# Telemetria.net
KiCad netlist of a schematic drawn in EAGLE
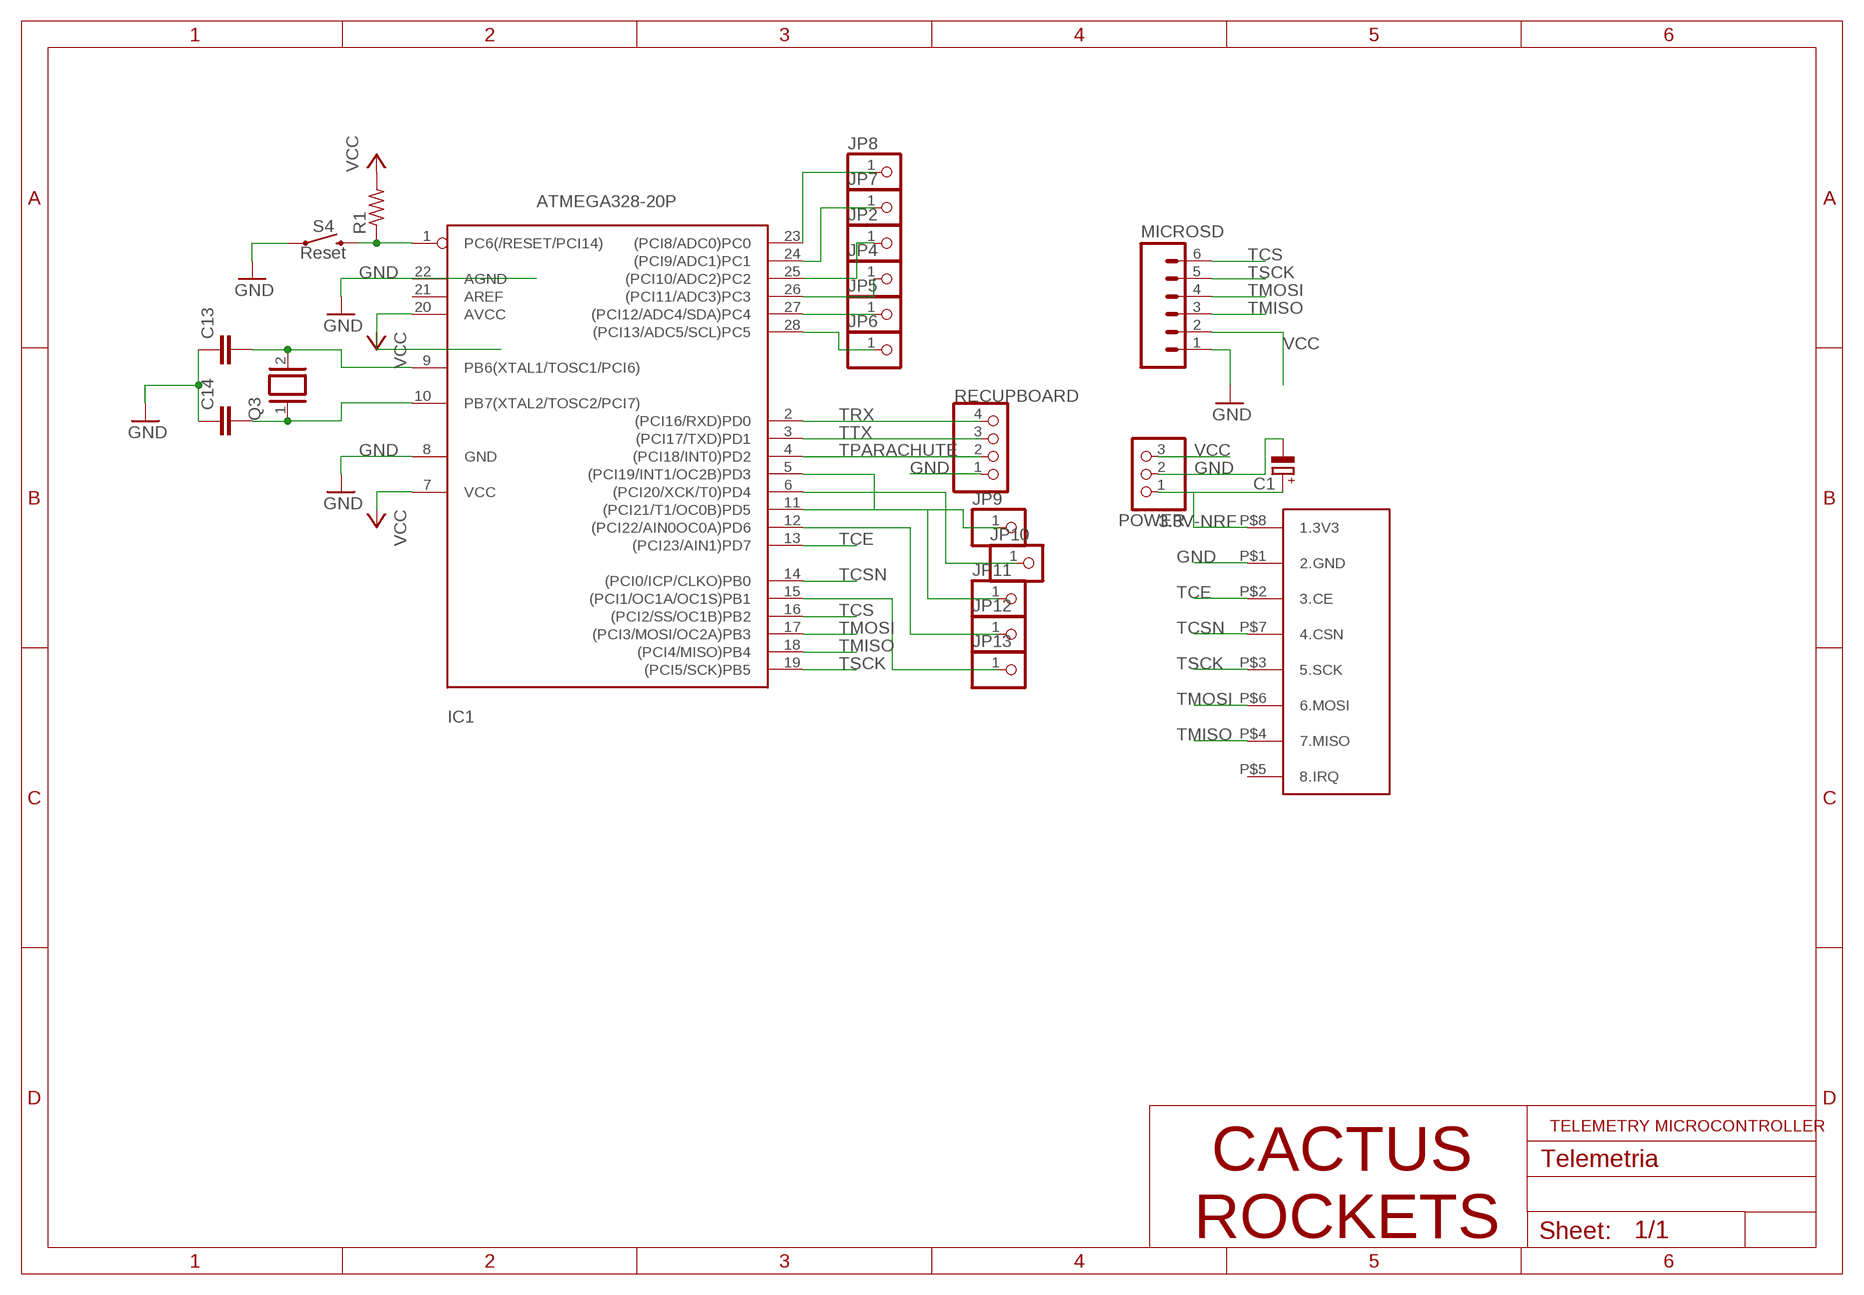
[diagram p0: schematic, sheet 1]

(export (version "E")
  (design (tool "Eeschema 10.0.6"))
  (components
    (comp (ref "C1")
      (value "CPOL-EUE1.8-4")
      (footprint "eagle-import:E1,8-4")
      (libsource (lib "eagle-import") (part "CPOL-EUE1.8-4"))
    )
    (comp (ref "C13")
      (value "C-EU025-025X050")
      (footprint "eagle-import:C025-025X050")
      (libsource (lib "eagle-import") (part "C-EU025-025X050"))
    )
    (comp (ref "C14")
      (value "C-EU025-025X050")
      (footprint "eagle-import:C025-025X050")
      (libsource (lib "eagle-import") (part "C-EU025-025X050"))
    )
    (comp (ref "IC1")
      (value "ATMEGA328-20P")
      (footprint "eagle-import:DIL28-3")
      (libsource (lib "eagle-import") (part "ATMEGA328P-20"))
    )
    (comp (ref "JP2")
      (value "PINHD-1X1")
      (footprint "eagle-import:1X01")
      (libsource (lib "eagle-import") (part "PINHD-1X1"))
    )
    (comp (ref "JP4")
      (value "PINHD-1X1")
      (footprint "eagle-import:1X01")
      (libsource (lib "eagle-import") (part "PINHD-1X1"))
    )
    (comp (ref "JP5")
      (value "PINHD-1X1")
      (footprint "eagle-import:1X01")
      (libsource (lib "eagle-import") (part "PINHD-1X1"))
    )
    (comp (ref "JP6")
      (value "PINHD-1X1")
      (footprint "eagle-import:1X01")
      (libsource (lib "eagle-import") (part "PINHD-1X1"))
    )
    (comp (ref "JP7")
      (value "PINHD-1X1")
      (footprint "eagle-import:1X01")
      (libsource (lib "eagle-import") (part "PINHD-1X1"))
    )
    (comp (ref "JP8")
      (value "PINHD-1X1")
      (footprint "eagle-import:1X01")
      (libsource (lib "eagle-import") (part "PINHD-1X1"))
    )
    (comp (ref "JP9")
      (value "PINHD-1X1")
      (footprint "eagle-import:1X01")
      (libsource (lib "eagle-import") (part "PINHD-1X1"))
    )
    (comp (ref "JP10")
      (value "PINHD-1X1")
      (footprint "eagle-import:1X01")
      (libsource (lib "eagle-import") (part "PINHD-1X1"))
    )
    (comp (ref "JP11")
      (value "PINHD-1X1")
      (footprint "eagle-import:1X01")
      (libsource (lib "eagle-import") (part "PINHD-1X1"))
    )
    (comp (ref "JP12")
      (value "PINHD-1X1")
      (footprint "eagle-import:1X01")
      (libsource (lib "eagle-import") (part "PINHD-1X1"))
    )
    (comp (ref "JP13")
      (value "PINHD-1X1")
      (footprint "eagle-import:1X01")
      (libsource (lib "eagle-import") (part "PINHD-1X1"))
    )
    (comp (ref "MICROSD")
      (value "M06NO_SILK_FEMALE_PTH")
      (footprint "eagle-import:1X06_NO_SILK")
      (libsource (lib "eagle-import") (part "M06NO_SILK_FEMALE_PTH"))
    )
    (comp (ref "POWER")
      (value "PINHD-1X3/90")
      (footprint "eagle-import:1X03_90")
      (libsource (lib "eagle-import") (part "PINHD-1X3/90"))
    )
    (comp (ref "Q3")
      (value "XTAL/S")
      (footprint "eagle-import:QS")
      (libsource (lib "eagle-import") (part "XTAL/S"))
    )
    (comp (ref "R1")
      (value "R-US_0207/10")
      (footprint "eagle-import:0207_10")
      (libsource (lib "eagle-import") (part "R-US_0207/10"))
    )
    (comp (ref "RECUPBOARD")
      (value "PINHD-1X4/90")
      (footprint "eagle-import:1X04_90")
      (libsource (lib "eagle-import") (part "PINHD-1X4/90"))
    )
    (comp (ref "S4")
      (value "Reset")
      (footprint "eagle-import:TACTILE_SWITCH_PTH_6.0MM")
      (libsource (lib "eagle-import") (part "MOMENTARY-SWITCH-SPST-PTH-6.0MM"))
    )
    (comp (ref "U$1")
      (value "NRF24L01+")
      (footprint "eagle-import:NRF24L01+")
      (libsource (lib "eagle-import") (part "NRF24L01+"))
    )
  )
  (nets
    (net (code "1") (name "/3.3V-NRF") (class "Default")
      (node (ref "C1") (pin "+") (pinfunction "+_+") (pintype "passive"))
      (node (ref "POWER") (pin "1") (pinfunction "1_1") (pintype "passive"))
      (node (ref "U$1") (pin "P$8") (pinfunction "1.3V3_P$8") (pintype "bidirectional"))
    )
    (net (code "2") (name "/TCE") (class "Default")
      (node (ref "IC1") (pin "13") (pinfunction "(PCI23/AIN1)PD7_13") (pintype "bidirectional"))
      (node (ref "U$1") (pin "P$2") (pinfunction "3.CE_P$2") (pintype "bidirectional"))
    )
    (net (code "3") (name "/TCS") (class "Default")
      (node (ref "IC1") (pin "16") (pinfunction "(PCI2/SS/OC1B)PB2_16") (pintype "bidirectional"))
      (node (ref "MICROSD") (pin "6") (pinfunction "6_6") (pintype "passive"))
    )
    (net (code "4") (name "/TCSN") (class "Default")
      (node (ref "IC1") (pin "14") (pinfunction "(PCI0/ICP/CLKO)PB0_14") (pintype "bidirectional"))
      (node (ref "U$1") (pin "P$7") (pinfunction "4.CSN_P$7") (pintype "bidirectional"))
    )
    (net (code "5") (name "/TMISO") (class "Default")
      (node (ref "IC1") (pin "18") (pinfunction "(PCI4/MISO)PB4_18") (pintype "bidirectional"))
      (node (ref "MICROSD") (pin "3") (pinfunction "3_3") (pintype "passive"))
      (node (ref "U$1") (pin "P$4") (pinfunction "7.MISO_P$4") (pintype "bidirectional"))
    )
    (net (code "6") (name "/TMOSI") (class "Default")
      (node (ref "IC1") (pin "17") (pinfunction "(PCI3/MOSI/OC2A)PB3_17") (pintype "bidirectional"))
      (node (ref "MICROSD") (pin "4") (pinfunction "4_4") (pintype "passive"))
      (node (ref "U$1") (pin "P$6") (pinfunction "6.MOSI_P$6") (pintype "bidirectional"))
    )
    (net (code "7") (name "/TPARACHUTE") (class "Default")
      (node (ref "IC1") (pin "4") (pinfunction "(PCI18/INT0)PD2_4") (pintype "bidirectional"))
      (node (ref "RECUPBOARD") (pin "2") (pinfunction "2_2") (pintype "passive"))
    )
    (net (code "8") (name "/TRX") (class "Default")
      (node (ref "IC1") (pin "2") (pinfunction "(PCI16/RXD)PD0_2") (pintype "bidirectional"))
      (node (ref "RECUPBOARD") (pin "4") (pinfunction "4_4") (pintype "passive"))
    )
    (net (code "9") (name "/TSCK") (class "Default")
      (node (ref "IC1") (pin "19") (pinfunction "(PCI5/SCK)PB5_19") (pintype "bidirectional"))
      (node (ref "MICROSD") (pin "5") (pinfunction "5_5") (pintype "passive"))
      (node (ref "U$1") (pin "P$3") (pinfunction "5.SCK_P$3") (pintype "bidirectional"))
    )
    (net (code "10") (name "/TTX") (class "Default")
      (node (ref "IC1") (pin "3") (pinfunction "(PCI17/TXD)PD1_3") (pintype "bidirectional"))
      (node (ref "RECUPBOARD") (pin "3") (pinfunction "3_3") (pintype "passive"))
    )
    (net (code "11") (name "GND") (class "Default")
      (node (ref "C1") (pin "-") (pinfunction "-_-") (pintype "passive"))
      (node (ref "C13") (pin "1") (pinfunction "1_1") (pintype "passive"))
      (node (ref "C14") (pin "1") (pinfunction "1_1") (pintype "passive"))
      (node (ref "IC1") (pin "22") (pinfunction "AGND_22") (pintype "bidirectional"))
      (node (ref "IC1") (pin "8") (pinfunction "GND_8") (pintype "bidirectional"))
      (node (ref "MICROSD") (pin "1") (pinfunction "1_1") (pintype "passive"))
      (node (ref "POWER") (pin "2") (pinfunction "2_2") (pintype "passive"))
      (node (ref "RECUPBOARD") (pin "1") (pinfunction "1_1") (pintype "passive"))
      (node (ref "S4") (pin "1") (pinfunction "1_1") (pintype "passive"))
      (node (ref "S4") (pin "2") (pinfunction "1_2") (pintype "passive"))
      (node (ref "U$1") (pin "P$1") (pinfunction "2.GND_P$1") (pintype "bidirectional"))
    )
    (net (code "12") (name "Net-(IC1-(PCI1{slash}OC1A{slash}OC1S)PB1)") (class "Default")
      (node (ref "IC1") (pin "15") (pinfunction "(PCI1/OC1A/OC1S)PB1_15") (pintype "bidirectional"))
      (node (ref "JP13") (pin "1") (pinfunction "1_1") (pintype "passive"))
    )
    (net (code "13") (name "Net-(IC1-(PCI8{slash}ADC0)PC0)") (class "Default")
      (node (ref "IC1") (pin "23") (pinfunction "(PCI8/ADC0)PC0_23") (pintype "bidirectional"))
      (node (ref "JP8") (pin "1") (pinfunction "1_1") (pintype "passive"))
    )
    (net (code "14") (name "Net-(IC1-(PCI9{slash}ADC1)PC1)") (class "Default")
      (node (ref "IC1") (pin "24") (pinfunction "(PCI9/ADC1)PC1_24") (pintype "bidirectional"))
      (node (ref "JP7") (pin "1") (pinfunction "1_1") (pintype "passive"))
    )
    (net (code "15") (name "Net-(IC1-(PCI10{slash}ADC2)PC2)") (class "Default")
      (node (ref "IC1") (pin "25") (pinfunction "(PCI10/ADC2)PC2_25") (pintype "bidirectional"))
      (node (ref "JP2") (pin "1") (pinfunction "1_1") (pintype "passive"))
    )
    (net (code "16") (name "Net-(IC1-(PCI11{slash}ADC3)PC3)") (class "Default")
      (node (ref "IC1") (pin "26") (pinfunction "(PCI11/ADC3)PC3_26") (pintype "bidirectional"))
      (node (ref "JP4") (pin "1") (pinfunction "1_1") (pintype "passive"))
    )
    (net (code "17") (name "Net-(IC1-(PCI12{slash}ADC4{slash}SDA)PC4)") (class "Default")
      (node (ref "IC1") (pin "27") (pinfunction "(PCI12/ADC4/SDA)PC4_27") (pintype "bidirectional"))
      (node (ref "JP5") (pin "1") (pinfunction "1_1") (pintype "passive"))
    )
    (net (code "18") (name "Net-(IC1-(PCI13{slash}ADC5{slash}SCL)PC5)") (class "Default")
      (node (ref "IC1") (pin "28") (pinfunction "(PCI13/ADC5/SCL)PC5_28") (pintype "bidirectional"))
      (node (ref "JP6") (pin "1") (pinfunction "1_1") (pintype "passive"))
    )
    (net (code "19") (name "Net-(IC1-(PCI19{slash}INT1{slash}OC2B)PD3)") (class "Default")
      (node (ref "IC1") (pin "5") (pinfunction "(PCI19/INT1/OC2B)PD3_5") (pintype "bidirectional"))
      (node (ref "JP9") (pin "1") (pinfunction "1_1") (pintype "passive"))
    )
    (net (code "20") (name "Net-(IC1-(PCI20{slash}XCK{slash}T0)PD4)") (class "Default")
      (node (ref "IC1") (pin "6") (pinfunction "(PCI20/XCK/T0)PD4_6") (pintype "bidirectional"))
      (node (ref "JP10") (pin "1") (pinfunction "1_1") (pintype "passive"))
    )
    (net (code "21") (name "Net-(IC1-(PCI21{slash}T1{slash}OC0B)PD5)") (class "Default")
      (node (ref "IC1") (pin "11") (pinfunction "(PCI21/T1/OC0B)PD5_11") (pintype "bidirectional"))
      (node (ref "JP11") (pin "1") (pinfunction "1_1") (pintype "passive"))
    )
    (net (code "22") (name "Net-(IC1-(PCI22{slash}AIN0OC0A)PD6)") (class "Default")
      (node (ref "IC1") (pin "12") (pinfunction "(PCI22/AIN0OC0A)PD6_12") (pintype "bidirectional"))
      (node (ref "JP12") (pin "1") (pinfunction "1_1") (pintype "passive"))
    )
    (net (code "23") (name "Net-(IC1-PB6(XTAL1{slash}TOSC1{slash}PCI6))") (class "Default")
      (node (ref "C13") (pin "2") (pinfunction "2_2") (pintype "passive"))
      (node (ref "IC1") (pin "9") (pinfunction "PB6(XTAL1/TOSC1/PCI6)_9") (pintype "bidirectional"))
      (node (ref "Q3") (pin "2") (pinfunction "2_2") (pintype "passive"))
    )
    (net (code "24") (name "Net-(IC1-PB7(XTAL2{slash}TOSC2{slash}PCI7))") (class "Default")
      (node (ref "C14") (pin "2") (pinfunction "2_2") (pintype "passive"))
      (node (ref "IC1") (pin "10") (pinfunction "PB7(XTAL2/TOSC2/PCI7)_10") (pintype "bidirectional"))
      (node (ref "Q3") (pin "1") (pinfunction "1_1") (pintype "passive"))
    )
    (net (code "25") (name "Net-(IC1-PC6({slash}RESET{slash}PCI14))") (class "Default")
      (node (ref "IC1") (pin "1") (pinfunction "PC6(/RESET/PCI14)_1") (pintype "bidirectional"))
      (node (ref "R1") (pin "1") (pinfunction "1_1") (pintype "passive"))
      (node (ref "S4") (pin "3") (pinfunction "2_3") (pintype "passive"))
      (node (ref "S4") (pin "4") (pinfunction "2_4") (pintype "passive"))
    )
    (net (code "26") (name "VCC") (class "Default")
      (node (ref "IC1") (pin "20") (pinfunction "AVCC_20") (pintype "bidirectional"))
      (node (ref "IC1") (pin "7") (pinfunction "VCC_7") (pintype "bidirectional"))
      (node (ref "MICROSD") (pin "2") (pinfunction "2_2") (pintype "passive"))
      (node (ref "POWER") (pin "3") (pinfunction "3_3") (pintype "passive"))
      (node (ref "R1") (pin "2") (pinfunction "2_2") (pintype "passive"))
    )
    (net (code "27") (name "unconnected-(IC1-AREF-Pad21)") (class "Default")
      (node (ref "IC1") (pin "21") (pinfunction "AREF_21") (pintype "bidirectional"))
    )
    (net (code "28") (name "unconnected-(U$1-8.IRQ-PadP$5)") (class "Default")
      (node (ref "U$1") (pin "P$5") (pinfunction "8.IRQ_P$5") (pintype "bidirectional"))
    )
  )
)
